# 08-STM32-01.net
KiCad netlist of a schematic drawn in Altium Designer
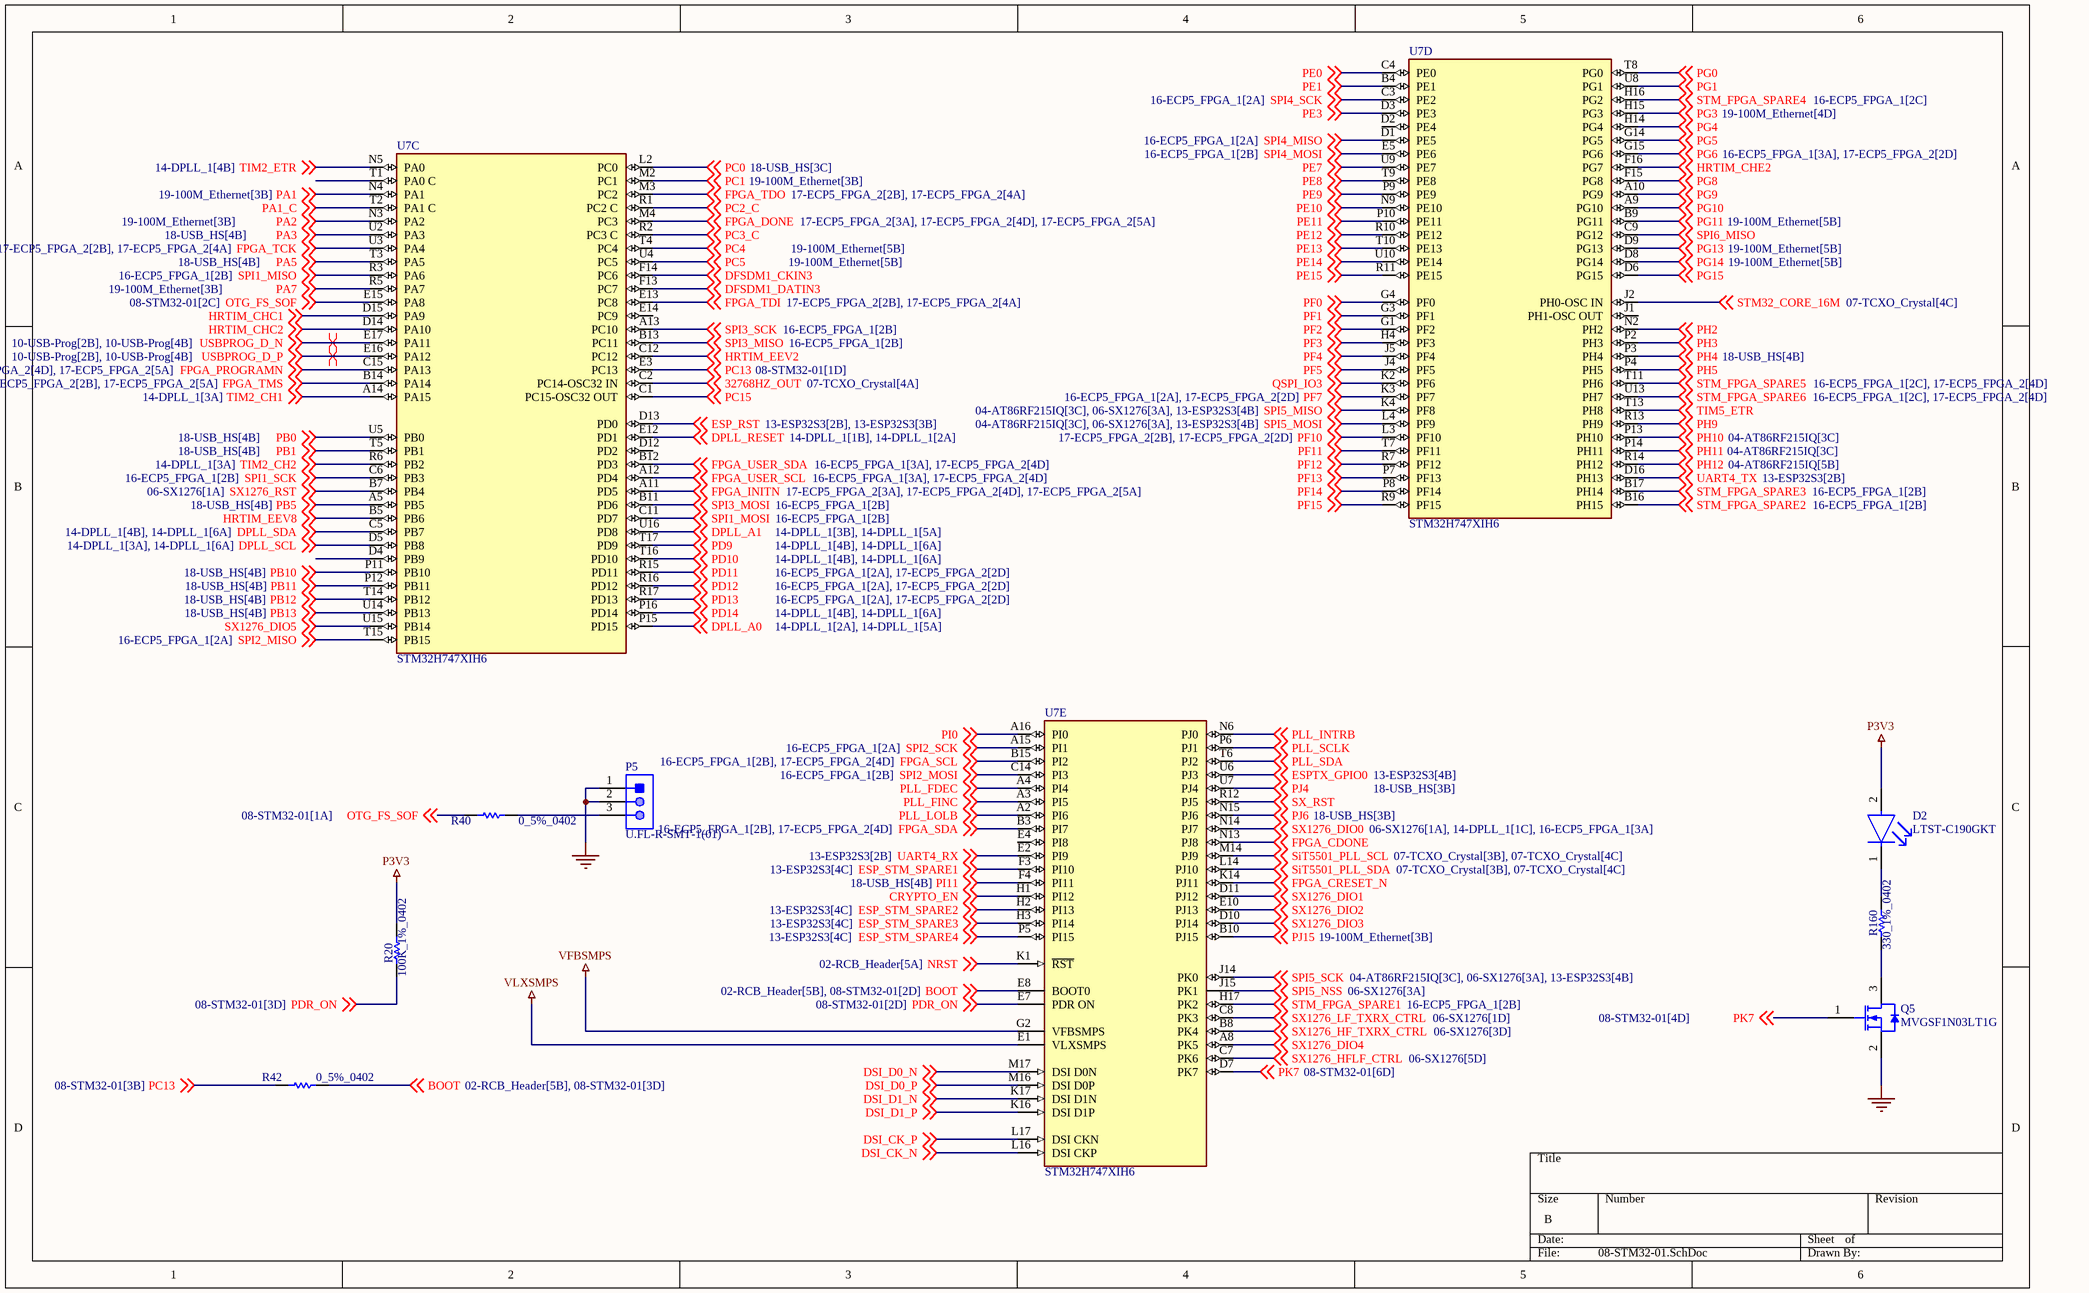
[diagram p0: 08-STM32-01.SchDoc]

(export (version "E")
  (design (tool "Eeschema 10.0.6"))
  (components
    (comp (ref "D2")
      (value "LTST-C190GKT")
      (footprint "FP-LTST-C190GKT-MFG")
      (description "LED GREEN CLEAR CHIP SMD")
      (fields (field (name "VOLTAGE") "2V"))
      (libsource (lib "Altium Content Vault") (part "8706943c75ba83719d021d2fdc84c58"))
    )
    (comp (ref "P5")
      (value "U.FL-R-SMT-1(01)")
      (footprint "HRS-U.FL-R-SMT-3_V")
      (description "Ultra Small Coaxial Connector, 6 GHz, -40 to 90 degC, 3-Pin SMD, RoHS, Bulk")
      (fields (field (name "MANUFACTURER") "Hirose Electric"))
      (libsource (lib "Altium Content Vault") (part "CN-1P-M-R3"))
    )
    (comp (ref "Q5")
      (value "MVGSF1N03LT1G")
      (footprint "ONSC-SOT-23-3-318-08_V")
      (description "Power MOSFET, 30 V, 2.1 A, Single N-Channel, 3-Pin SOT-23, Pb-Free, Tape and Reel")
      (fields (field (name "MANUFACTURER") "On Semiconductor"))
      (libsource (lib "Altium Content Vault") (part "ONSC-NMOS-G1S2D3-3"))
    )
    (comp (ref "R20")
      (value "100K_1%_0402")
      (footprint "RESC1005X40X25ML05T10")
      (fields (field (name "MANUFACTURER") "Yageo") (field (name "PART NUMBER") "RC0402FR-13100KL"))
      (libsource (lib "Altium Content Vault") (part "RES"))
    )
    (comp (ref "R40")
      (value "0_5%_0402")
      (footprint "RESC1005X40X25NL05T10")
      (fields (field (name "MANUFACTURER") "Panasonic") (field (name "PART NUMBER") "ERJ-U020R00X"))
      (libsource (lib "Altium Content Vault") (part "RES"))
    )
    (comp (ref "R42")
      (value "0_5%_0402")
      (footprint "RESC1005X40X25NL05T10")
      (fields (field (name "MANUFACTURER") "Panasonic") (field (name "PART NUMBER") "ERJ-U020R00X"))
      (libsource (lib "Altium Content Vault") (part "RES"))
    )
    (comp (ref "R160")
      (value "330_1%_0402")
      (footprint "RESC1005X40X25NL10T10")
      (fields (field (name "MANUFACTURER") "Panasonic") (field (name "PART NUMBER") "ERA-2AED331X"))
      (libsource (lib "Altium Content Vault") (part "RES"))
    )
    (comp (ref "U7")
      (value "STM32H747XIH6")
      (footprint "FP-TFBGA240+25-A07U-MFG")
      (description "HIGH-PERFORMANCE AND DSP WITH DP")
      (fields
        (field (name "MANUFACTURER") "STMicroelectronics")
        (field (name "OCTOPART") "https://octopart.com/stm32h747xih6-stmicroelectronics-100293943")
      )
      (libsource (lib "Altium Content Vault") (part "41f839bdfd00d9510c8672f0f410bfb"))
    )
  )
  (nets
    (net (code "1") (name "32768HZ_OUT") (class "Default")
      (node (ref "U7") (pin "C2") (pinfunction "PC14-OSC32_IN_C2") (pintype "bidirectional"))
    )
    (net (code "2") (name "BOOT") (class "Default")
      (node (ref "R42") (pin "2") (pinfunction "2_2") (pintype "passive"))
      (node (ref "U7") (pin "E8") (pinfunction "BOOT0_E8") (pintype "passive"))
    )
    (net (code "3") (name "CRYPTO_EN") (class "Default")
      (node (ref "U7") (pin "H1") (pinfunction "PI12_H1") (pintype "bidirectional"))
    )
    (net (code "4") (name "DFSDM1_CKIN3") (class "Default")
      (node (ref "U7") (pin "F14") (pinfunction "PC6_F14") (pintype "bidirectional"))
    )
    (net (code "5") (name "DFSDM1_DATIN3") (class "Default")
      (node (ref "U7") (pin "F13") (pinfunction "PC7_F13") (pintype "bidirectional"))
    )
    (net (code "6") (name "DPLL_A0") (class "Default")
      (node (ref "U7") (pin "P15") (pinfunction "PD15_P15") (pintype "bidirectional"))
    )
    (net (code "7") (name "DPLL_A1") (class "Default")
      (node (ref "U7") (pin "U16") (pinfunction "PD8_U16") (pintype "bidirectional"))
    )
    (net (code "8") (name "DPLL_RESET") (class "Default")
      (node (ref "U7") (pin "E12") (pinfunction "PD1_E12") (pintype "bidirectional"))
    )
    (net (code "9") (name "DPLL_SCL") (class "Default")
      (node (ref "U7") (pin "D5") (pinfunction "PB8_D5") (pintype "bidirectional"))
    )
    (net (code "10") (name "DPLL_SDA") (class "Default")
      (node (ref "U7") (pin "C5") (pinfunction "PB7_C5") (pintype "bidirectional"))
    )
    (net (code "11") (name "DSI_CK_N") (class "Default")
      (node (ref "U7") (pin "L16") (pinfunction "DSI_CKP_L16") (pintype "input"))
    )
    (net (code "12") (name "DSI_CK_P") (class "Default")
      (node (ref "U7") (pin "L17") (pinfunction "DSI_CKN_L17") (pintype "input"))
    )
    (net (code "13") (name "DSI_D0_N") (class "Default")
      (node (ref "U7") (pin "M17") (pinfunction "DSI_D0N_M17") (pintype "input"))
    )
    (net (code "14") (name "DSI_D0_P") (class "Default")
      (node (ref "U7") (pin "M16") (pinfunction "DSI_D0P_M16") (pintype "input"))
    )
    (net (code "15") (name "DSI_D1_N") (class "Default")
      (node (ref "U7") (pin "K17") (pinfunction "DSI_D1N_K17") (pintype "input"))
    )
    (net (code "16") (name "DSI_D1_P") (class "Default")
      (node (ref "U7") (pin "K16") (pinfunction "DSI_D1P_K16") (pintype "input"))
    )
    (net (code "17") (name "ESPTX_GPIO0") (class "Default")
      (node (ref "U7") (pin "U6") (pinfunction "PJ3_U6") (pintype "bidirectional"))
    )
    (net (code "18") (name "ESP_RST") (class "Default")
      (node (ref "U7") (pin "D13") (pinfunction "PD0_D13") (pintype "bidirectional"))
    )
    (net (code "19") (name "ESP_STM_SPARE1") (class "Default")
      (node (ref "U7") (pin "F3") (pinfunction "PI10_F3") (pintype "bidirectional"))
    )
    (net (code "20") (name "ESP_STM_SPARE2") (class "Default")
      (node (ref "U7") (pin "H2") (pinfunction "PI13_H2") (pintype "bidirectional"))
    )
    (net (code "21") (name "ESP_STM_SPARE3") (class "Default")
      (node (ref "U7") (pin "H3") (pinfunction "PI14_H3") (pintype "bidirectional"))
    )
    (net (code "22") (name "ESP_STM_SPARE4") (class "Default")
      (node (ref "U7") (pin "P5") (pinfunction "PI15_P5") (pintype "bidirectional"))
    )
    (net (code "23") (name "FPGA_CDONE") (class "Default")
      (node (ref "U7") (pin "N13") (pinfunction "PJ8_N13") (pintype "bidirectional"))
    )
    (net (code "24") (name "FPGA_CRESET_N") (class "Default")
      (node (ref "U7") (pin "K14") (pinfunction "PJ11_K14") (pintype "bidirectional"))
    )
    (net (code "25") (name "FPGA_DONE") (class "Default")
      (node (ref "U7") (pin "M4") (pinfunction "PC3_M4") (pintype "bidirectional"))
    )
    (net (code "26") (name "FPGA_INITN") (class "Default")
      (node (ref "U7") (pin "A11") (pinfunction "PD5_A11") (pintype "bidirectional"))
    )
    (net (code "27") (name "FPGA_PROGRAMN") (class "Default")
      (node (ref "U7") (pin "C15") (pinfunction "PA13_C15") (pintype "bidirectional"))
    )
    (net (code "28") (name "FPGA_SCL") (class "Default")
      (node (ref "U7") (pin "B15") (pinfunction "PI2_B15") (pintype "bidirectional"))
    )
    (net (code "29") (name "FPGA_SDA") (class "Default")
      (node (ref "U7") (pin "B3") (pinfunction "PI7_B3") (pintype "bidirectional"))
    )
    (net (code "30") (name "FPGA_TCK") (class "Default")
      (node (ref "U7") (pin "U3") (pinfunction "PA4_U3") (pintype "bidirectional"))
    )
    (net (code "31") (name "FPGA_TDI") (class "Default")
      (node (ref "U7") (pin "E13") (pinfunction "PC8_E13") (pintype "bidirectional"))
    )
    (net (code "32") (name "FPGA_TDO") (class "Default")
      (node (ref "U7") (pin "M3") (pinfunction "PC2_M3") (pintype "bidirectional"))
    )
    (net (code "33") (name "FPGA_TMS") (class "Default")
      (node (ref "U7") (pin "B14") (pinfunction "PA14_B14") (pintype "bidirectional"))
    )
    (net (code "34") (name "FPGA_USER_SCL") (class "Default")
      (node (ref "U7") (pin "A12") (pinfunction "PD4_A12") (pintype "bidirectional"))
    )
    (net (code "35") (name "FPGA_USER_SDA") (class "Default")
      (node (ref "U7") (pin "B12") (pinfunction "PD3_B12") (pintype "bidirectional"))
    )
    (net (code "36") (name "GND") (class "Default")
      (node (ref "P5") (pin "1") (pinfunction "1_1") (pintype "passive"))
      (node (ref "P5") (pin "2") (pinfunction "2_2") (pintype "passive"))
      (node (ref "Q5") (pin "2") (pinfunction "S_2") (pintype "passive"))
    )
    (net (code "37") (name "HRTIM_CHC1") (class "Default")
      (node (ref "U7") (pin "D15") (pinfunction "PA9_D15") (pintype "bidirectional"))
    )
    (net (code "38") (name "HRTIM_CHC2") (class "Default")
      (node (ref "U7") (pin "D14") (pinfunction "PA10_D14") (pintype "bidirectional"))
    )
    (net (code "39") (name "HRTIM_CHE2") (class "Default")
      (node (ref "U7") (pin "F16") (pinfunction "PG7_F16") (pintype "bidirectional"))
    )
    (net (code "40") (name "HRTIM_EEV2") (class "Default")
      (node (ref "U7") (pin "C12") (pinfunction "PC12_C12") (pintype "bidirectional"))
    )
    (net (code "41") (name "HRTIM_EEV8") (class "Default")
      (node (ref "U7") (pin "B5") (pinfunction "PB6_B5") (pintype "bidirectional"))
    )
    (net (code "42") (name "NRST") (class "Default")
      (node (ref "U7") (pin "K1") (pinfunction "~{RST}_K1") (pintype "input"))
    )
    (net (code "43") (name "Net-(D2-C)") (class "Default")
      (node (ref "D2") (pin "1") (pinfunction "C_1") (pintype "passive"))
      (node (ref "R160") (pin "2") (pinfunction "2_2") (pintype "passive"))
    )
    (net (code "44") (name "Net-(P5-Pad3)") (class "Default")
      (node (ref "P5") (pin "3") (pinfunction "3_3") (pintype "passive"))
      (node (ref "R40") (pin "2") (pinfunction "2_2") (pintype "passive"))
    )
    (net (code "45") (name "Net-(Q5-D)") (class "Default")
      (node (ref "Q5") (pin "3") (pinfunction "D_3") (pintype "passive"))
      (node (ref "R160") (pin "1") (pinfunction "1_1") (pintype "passive"))
    )
    (net (code "46") (name "OTG_FS_SOF") (class "Default")
      (node (ref "R40") (pin "1") (pinfunction "1_1") (pintype "passive"))
      (node (ref "U7") (pin "E15") (pinfunction "PA8_E15") (pintype "bidirectional"))
    )
    (net (code "47") (name "P3V3") (class "Default")
      (node (ref "D2") (pin "2") (pinfunction "A_2") (pintype "passive"))
      (node (ref "R20") (pin "2") (pinfunction "2_2") (pintype "passive"))
    )
    (net (code "48") (name "PA1") (class "Default")
      (node (ref "U7") (pin "N4") (pinfunction "PA1_N4") (pintype "bidirectional"))
    )
    (net (code "49") (name "PA1_C") (class "Default")
      (node (ref "U7") (pin "T2") (pinfunction "PA1_C_T2") (pintype "bidirectional"))
    )
    (net (code "50") (name "PA2") (class "Default")
      (node (ref "U7") (pin "N3") (pinfunction "PA2_N3") (pintype "bidirectional"))
    )
    (net (code "51") (name "PA3") (class "Default")
      (node (ref "U7") (pin "U2") (pinfunction "PA3_U2") (pintype "bidirectional"))
    )
    (net (code "52") (name "PA5") (class "Default")
      (node (ref "U7") (pin "T3") (pinfunction "PA5_T3") (pintype "bidirectional"))
    )
    (net (code "53") (name "PA7") (class "Default")
      (node (ref "U7") (pin "R5") (pinfunction "PA7_R5") (pintype "bidirectional"))
    )
    (net (code "54") (name "PB0") (class "Default")
      (node (ref "U7") (pin "U5") (pinfunction "PB0_U5") (pintype "bidirectional"))
    )
    (net (code "55") (name "PB1") (class "Default")
      (node (ref "U7") (pin "T5") (pinfunction "PB1_T5") (pintype "bidirectional"))
    )
    (net (code "56") (name "PB5") (class "Default")
      (node (ref "U7") (pin "A5") (pinfunction "PB5_A5") (pintype "bidirectional"))
    )
    (net (code "57") (name "PB10") (class "Default")
      (node (ref "U7") (pin "P11") (pinfunction "PB10_P11") (pintype "bidirectional"))
    )
    (net (code "58") (name "PB11") (class "Default")
      (node (ref "U7") (pin "P12") (pinfunction "PB11_P12") (pintype "bidirectional"))
    )
    (net (code "59") (name "PB12") (class "Default")
      (node (ref "U7") (pin "T14") (pinfunction "PB12_T14") (pintype "bidirectional"))
    )
    (net (code "60") (name "PB13") (class "Default")
      (node (ref "U7") (pin "U14") (pinfunction "PB13_U14") (pintype "bidirectional"))
    )
    (net (code "61") (name "PC0") (class "Default")
      (node (ref "U7") (pin "L2") (pinfunction "PC0_L2") (pintype "bidirectional"))
    )
    (net (code "62") (name "PC1") (class "Default")
      (node (ref "U7") (pin "M2") (pinfunction "PC1_M2") (pintype "bidirectional"))
    )
    (net (code "63") (name "PC2_C") (class "Default")
      (node (ref "U7") (pin "R1") (pinfunction "PC2_C_R1") (pintype "bidirectional"))
    )
    (net (code "64") (name "PC3_C") (class "Default")
      (node (ref "U7") (pin "R2") (pinfunction "PC3_C_R2") (pintype "bidirectional"))
    )
    (net (code "65") (name "PC4") (class "Default")
      (node (ref "U7") (pin "T4") (pinfunction "PC4_T4") (pintype "bidirectional"))
    )
    (net (code "66") (name "PC5") (class "Default")
      (node (ref "U7") (pin "U4") (pinfunction "PC5_U4") (pintype "bidirectional"))
    )
    (net (code "67") (name "PC13") (class "Default")
      (node (ref "R42") (pin "1") (pinfunction "1_1") (pintype "passive"))
      (node (ref "U7") (pin "E3") (pinfunction "PC13_E3") (pintype "bidirectional"))
    )
    (net (code "68") (name "PC15") (class "Default")
      (node (ref "U7") (pin "C1") (pinfunction "PC15-OSC32_OUT_C1") (pintype "bidirectional"))
    )
    (net (code "69") (name "PD9") (class "Default")
      (node (ref "U7") (pin "T17") (pinfunction "PD9_T17") (pintype "bidirectional"))
    )
    (net (code "70") (name "PD10") (class "Default")
      (node (ref "U7") (pin "T16") (pinfunction "PD10_T16") (pintype "bidirectional"))
    )
    (net (code "71") (name "PD11") (class "Default")
      (node (ref "U7") (pin "R15") (pinfunction "PD11_R15") (pintype "bidirectional"))
    )
    (net (code "72") (name "PD12") (class "Default")
      (node (ref "U7") (pin "R16") (pinfunction "PD12_R16") (pintype "bidirectional"))
    )
    (net (code "73") (name "PD13") (class "Default")
      (node (ref "U7") (pin "R17") (pinfunction "PD13_R17") (pintype "bidirectional"))
    )
    (net (code "74") (name "PD14") (class "Default")
      (node (ref "U7") (pin "P16") (pinfunction "PD14_P16") (pintype "bidirectional"))
    )
    (net (code "75") (name "PDR_ON") (class "Default")
      (node (ref "R20") (pin "1") (pinfunction "1_1") (pintype "passive"))
      (node (ref "U7") (pin "E7") (pinfunction "PDR_ON_E7") (pintype "power_in"))
    )
    (net (code "76") (name "PE0") (class "Default")
      (node (ref "U7") (pin "C4") (pinfunction "PE0_C4") (pintype "bidirectional"))
    )
    (net (code "77") (name "PE1") (class "Default")
      (node (ref "U7") (pin "B4") (pinfunction "PE1_B4") (pintype "bidirectional"))
    )
    (net (code "78") (name "PE3") (class "Default")
      (node (ref "U7") (pin "D3") (pinfunction "PE3_D3") (pintype "bidirectional"))
    )
    (net (code "79") (name "PE7") (class "Default")
      (node (ref "U7") (pin "U9") (pinfunction "PE7_U9") (pintype "bidirectional"))
    )
    (net (code "80") (name "PE8") (class "Default")
      (node (ref "U7") (pin "T9") (pinfunction "PE8_T9") (pintype "bidirectional"))
    )
    (net (code "81") (name "PE9") (class "Default")
      (node (ref "U7") (pin "P9") (pinfunction "PE9_P9") (pintype "bidirectional"))
    )
    (net (code "82") (name "PE10") (class "Default")
      (node (ref "U7") (pin "N9") (pinfunction "PE10_N9") (pintype "bidirectional"))
    )
    (net (code "83") (name "PE11") (class "Default")
      (node (ref "U7") (pin "P10") (pinfunction "PE11_P10") (pintype "bidirectional"))
    )
    (net (code "84") (name "PE12") (class "Default")
      (node (ref "U7") (pin "R10") (pinfunction "PE12_R10") (pintype "bidirectional"))
    )
    (net (code "85") (name "PE13") (class "Default")
      (node (ref "U7") (pin "T10") (pinfunction "PE13_T10") (pintype "bidirectional"))
    )
    (net (code "86") (name "PE14") (class "Default")
      (node (ref "U7") (pin "U10") (pinfunction "PE14_U10") (pintype "bidirectional"))
    )
    (net (code "87") (name "PE15") (class "Default")
      (node (ref "U7") (pin "R11") (pinfunction "PE15_R11") (pintype "bidirectional"))
    )
    (net (code "88") (name "PF0") (class "Default")
      (node (ref "U7") (pin "G4") (pinfunction "PF0_G4") (pintype "bidirectional"))
    )
    (net (code "89") (name "PF1") (class "Default")
      (node (ref "U7") (pin "G3") (pinfunction "PF1_G3") (pintype "bidirectional"))
    )
    (net (code "90") (name "PF2") (class "Default")
      (node (ref "U7") (pin "G1") (pinfunction "PF2_G1") (pintype "bidirectional"))
    )
    (net (code "91") (name "PF3") (class "Default")
      (node (ref "U7") (pin "H4") (pinfunction "PF3_H4") (pintype "bidirectional"))
    )
    (net (code "92") (name "PF4") (class "Default")
      (node (ref "U7") (pin "J5") (pinfunction "PF4_J5") (pintype "bidirectional"))
    )
    (net (code "93") (name "PF5") (class "Default")
      (node (ref "U7") (pin "J4") (pinfunction "PF5_J4") (pintype "bidirectional"))
    )
    (net (code "94") (name "PF7") (class "Default")
      (node (ref "U7") (pin "K3") (pinfunction "PF7_K3") (pintype "bidirectional"))
    )
    (net (code "95") (name "PF10") (class "Default")
      (node (ref "U7") (pin "L3") (pinfunction "PF10_L3") (pintype "bidirectional"))
    )
    (net (code "96") (name "PF11") (class "Default")
      (node (ref "U7") (pin "T7") (pinfunction "PF11_T7") (pintype "bidirectional"))
    )
    (net (code "97") (name "PF12") (class "Default")
      (node (ref "U7") (pin "R7") (pinfunction "PF12_R7") (pintype "bidirectional"))
    )
    (net (code "98") (name "PF13") (class "Default")
      (node (ref "U7") (pin "P7") (pinfunction "PF13_P7") (pintype "bidirectional"))
    )
    (net (code "99") (name "PF14") (class "Default")
      (node (ref "U7") (pin "P8") (pinfunction "PF14_P8") (pintype "bidirectional"))
    )
    (net (code "100") (name "PF15") (class "Default")
      (node (ref "U7") (pin "R9") (pinfunction "PF15_R9") (pintype "bidirectional"))
    )
    (net (code "101") (name "PG0") (class "Default")
      (node (ref "U7") (pin "T8") (pinfunction "PG0_T8") (pintype "bidirectional"))
    )
    (net (code "102") (name "PG1") (class "Default")
      (node (ref "U7") (pin "U8") (pinfunction "PG1_U8") (pintype "bidirectional"))
    )
    (net (code "103") (name "PG3") (class "Default")
      (node (ref "U7") (pin "H15") (pinfunction "PG3_H15") (pintype "bidirectional"))
    )
    (net (code "104") (name "PG4") (class "Default")
      (node (ref "U7") (pin "H14") (pinfunction "PG4_H14") (pintype "bidirectional"))
    )
    (net (code "105") (name "PG5") (class "Default")
      (node (ref "U7") (pin "G14") (pinfunction "PG5_G14") (pintype "bidirectional"))
    )
    (net (code "106") (name "PG6") (class "Default")
      (node (ref "U7") (pin "G15") (pinfunction "PG6_G15") (pintype "bidirectional"))
    )
    (net (code "107") (name "PG8") (class "Default")
      (node (ref "U7") (pin "F15") (pinfunction "PG8_F15") (pintype "bidirectional"))
    )
    (net (code "108") (name "PG9") (class "Default")
      (node (ref "U7") (pin "A10") (pinfunction "PG9_A10") (pintype "bidirectional"))
    )
    (net (code "109") (name "PG10") (class "Default")
      (node (ref "U7") (pin "A9") (pinfunction "PG10_A9") (pintype "bidirectional"))
    )
    (net (code "110") (name "PG11") (class "Default")
      (node (ref "U7") (pin "B9") (pinfunction "PG11_B9") (pintype "bidirectional"))
    )
    (net (code "111") (name "PG13") (class "Default")
      (node (ref "U7") (pin "D9") (pinfunction "PG13_D9") (pintype "bidirectional"))
    )
    (net (code "112") (name "PG14") (class "Default")
      (node (ref "U7") (pin "D8") (pinfunction "PG14_D8") (pintype "bidirectional"))
    )
    (net (code "113") (name "PG15") (class "Default")
      (node (ref "U7") (pin "D6") (pinfunction "PG15_D6") (pintype "bidirectional"))
    )
    (net (code "114") (name "PH2") (class "Default")
      (node (ref "U7") (pin "N2") (pinfunction "PH2_N2") (pintype "bidirectional"))
    )
    (net (code "115") (name "PH3") (class "Default")
      (node (ref "U7") (pin "P2") (pinfunction "PH3_P2") (pintype "bidirectional"))
    )
    (net (code "116") (name "PH4") (class "Default")
      (node (ref "U7") (pin "P3") (pinfunction "PH4_P3") (pintype "bidirectional"))
    )
    (net (code "117") (name "PH5") (class "Default")
      (node (ref "U7") (pin "P4") (pinfunction "PH5_P4") (pintype "bidirectional"))
    )
    (net (code "118") (name "PH9") (class "Default")
      (node (ref "U7") (pin "R13") (pinfunction "PH9_R13") (pintype "bidirectional"))
    )
    (net (code "119") (name "PH10") (class "Default")
      (node (ref "U7") (pin "P13") (pinfunction "PH10_P13") (pintype "bidirectional"))
    )
    (net (code "120") (name "PH11") (class "Default")
      (node (ref "U7") (pin "P14") (pinfunction "PH11_P14") (pintype "bidirectional"))
    )
    (net (code "121") (name "PH12") (class "Default")
      (node (ref "U7") (pin "R14") (pinfunction "PH12_R14") (pintype "bidirectional"))
    )
    (net (code "122") (name "PI0") (class "Default")
      (node (ref "U7") (pin "A16") (pinfunction "PI0_A16") (pintype "bidirectional"))
    )
    (net (code "123") (name "PI11") (class "Default")
      (node (ref "U7") (pin "F4") (pinfunction "PI11_F4") (pintype "bidirectional"))
    )
    (net (code "124") (name "PJ4") (class "Default")
      (node (ref "U7") (pin "U7") (pinfunction "PJ4_U7") (pintype "bidirectional"))
    )
    (net (code "125") (name "PJ6") (class "Default")
      (node (ref "U7") (pin "N15") (pinfunction "PJ6_N15") (pintype "bidirectional"))
    )
    (net (code "126") (name "PJ15") (class "Default")
      (node (ref "U7") (pin "B10") (pinfunction "PJ15_B10") (pintype "bidirectional"))
    )
    (net (code "127") (name "PK7") (class "Default")
      (node (ref "Q5") (pin "1") (pinfunction "G_1") (pintype "passive"))
      (node (ref "U7") (pin "D7") (pinfunction "PK7_D7") (pintype "bidirectional"))
    )
    (net (code "128") (name "PLL_FDEC") (class "Default")
      (node (ref "U7") (pin "A4") (pinfunction "PI4_A4") (pintype "bidirectional"))
    )
    (net (code "129") (name "PLL_FINC") (class "Default")
      (node (ref "U7") (pin "A3") (pinfunction "PI5_A3") (pintype "bidirectional"))
    )
    (net (code "130") (name "PLL_INTRB") (class "Default")
      (node (ref "U7") (pin "N6") (pinfunction "PJ0_N6") (pintype "bidirectional"))
    )
    (net (code "131") (name "PLL_LOLB") (class "Default")
      (node (ref "U7") (pin "A2") (pinfunction "PI6_A2") (pintype "bidirectional"))
    )
    (net (code "132") (name "PLL_SCLK") (class "Default")
      (node (ref "U7") (pin "P6") (pinfunction "PJ1_P6") (pintype "bidirectional"))
    )
    (net (code "133") (name "PLL_SDA") (class "Default")
      (node (ref "U7") (pin "T6") (pinfunction "PJ2_T6") (pintype "bidirectional"))
    )
    (net (code "134") (name "QSPI_IO3") (class "Default")
      (node (ref "U7") (pin "K2") (pinfunction "PF6_K2") (pintype "bidirectional"))
    )
    (net (code "135") (name "SPI1_MISO") (class "Default")
      (node (ref "U7") (pin "R3") (pinfunction "PA6_R3") (pintype "bidirectional"))
    )
    (net (code "136") (name "SPI1_MOSI") (class "Default")
      (node (ref "U7") (pin "C11") (pinfunction "PD7_C11") (pintype "bidirectional"))
    )
    (net (code "137") (name "SPI1_SCK") (class "Default")
      (node (ref "U7") (pin "C6") (pinfunction "PB3_C6") (pintype "bidirectional"))
    )
    (net (code "138") (name "SPI2_MISO") (class "Default")
      (node (ref "U7") (pin "T15") (pinfunction "PB15_T15") (pintype "bidirectional"))
    )
    (net (code "139") (name "SPI2_MOSI") (class "Default")
      (node (ref "U7") (pin "C14") (pinfunction "PI3_C14") (pintype "bidirectional"))
    )
    (net (code "140") (name "SPI2_SCK") (class "Default")
      (node (ref "U7") (pin "A15") (pinfunction "PI1_A15") (pintype "bidirectional"))
    )
    (net (code "141") (name "SPI3_MISO") (class "Default")
      (node (ref "U7") (pin "B13") (pinfunction "PC11_B13") (pintype "bidirectional"))
    )
    (net (code "142") (name "SPI3_MOSI") (class "Default")
      (node (ref "U7") (pin "B11") (pinfunction "PD6_B11") (pintype "bidirectional"))
    )
    (net (code "143") (name "SPI3_SCK") (class "Default")
      (node (ref "U7") (pin "A13") (pinfunction "PC10_A13") (pintype "bidirectional"))
    )
    (net (code "144") (name "SPI4_MISO") (class "Default")
      (node (ref "U7") (pin "D1") (pinfunction "PE5_D1") (pintype "bidirectional"))
    )
    (net (code "145") (name "SPI4_MOSI") (class "Default")
      (node (ref "U7") (pin "E5") (pinfunction "PE6_E5") (pintype "bidirectional"))
    )
    (net (code "146") (name "SPI4_SCK") (class "Default")
      (node (ref "U7") (pin "C3") (pinfunction "PE2_C3") (pintype "bidirectional"))
    )
    (net (code "147") (name "SPI5_MISO") (class "Default")
      (node (ref "U7") (pin "K4") (pinfunction "PF8_K4") (pintype "bidirectional"))
    )
    (net (code "148") (name "SPI5_MOSI") (class "Default")
      (node (ref "U7") (pin "L4") (pinfunction "PF9_L4") (pintype "bidirectional"))
    )
    (net (code "149") (name "SPI5_NSS") (class "Default")
      (node (ref "U7") (pin "J15") (pinfunction "PK1_J15") (pintype "passive"))
    )
    (net (code "150") (name "SPI5_SCK") (class "Default")
      (node (ref "U7") (pin "J14") (pinfunction "PK0_J14") (pintype "bidirectional"))
    )
    (net (code "151") (name "SPI6_MISO") (class "Default")
      (node (ref "U7") (pin "C9") (pinfunction "PG12_C9") (pintype "bidirectional"))
    )
    (net (code "152") (name "STM32_CORE_16M") (class "Default")
      (node (ref "U7") (pin "J2") (pinfunction "PH0-OSC_IN_J2") (pintype "bidirectional"))
    )
    (net (code "153") (name "STM_FPGA_SPARE1") (class "Default")
      (node (ref "U7") (pin "H17") (pinfunction "PK2_H17") (pintype "bidirectional"))
    )
    (net (code "154") (name "STM_FPGA_SPARE2") (class "Default")
      (node (ref "U7") (pin "B16") (pinfunction "PH15_B16") (pintype "bidirectional"))
    )
    (net (code "155") (name "STM_FPGA_SPARE3") (class "Default")
      (node (ref "U7") (pin "B17") (pinfunction "PH14_B17") (pintype "bidirectional"))
    )
    (net (code "156") (name "STM_FPGA_SPARE4") (class "Default")
      (node (ref "U7") (pin "H16") (pinfunction "PG2_H16") (pintype "bidirectional"))
    )
    (net (code "157") (name "STM_FPGA_SPARE5") (class "Default")
      (node (ref "U7") (pin "T11") (pinfunction "PH6_T11") (pintype "bidirectional"))
    )
    (net (code "158") (name "STM_FPGA_SPARE6") (class "Default")
      (node (ref "U7") (pin "U13") (pinfunction "PH7_U13") (pintype "bidirectional"))
    )
    (net (code "159") (name "SX1276_DIO0") (class "Default")
      (node (ref "U7") (pin "N14") (pinfunction "PJ7_N14") (pintype "bidirectional"))
    )
    (net (code "160") (name "SX1276_DIO1") (class "Default")
      (node (ref "U7") (pin "D11") (pinfunction "PJ12_D11") (pintype "bidirectional"))
    )
    (net (code "161") (name "SX1276_DIO2") (class "Default")
      (node (ref "U7") (pin "E10") (pinfunction "PJ13_E10") (pintype "bidirectional"))
    )
    (net (code "162") (name "SX1276_DIO3") (class "Default")
      (node (ref "U7") (pin "D10") (pinfunction "PJ14_D10") (pintype "bidirectional"))
    )
    (net (code "163") (name "SX1276_DIO4") (class "Default")
      (node (ref "U7") (pin "A8") (pinfunction "PK5_A8") (pintype "bidirectional"))
    )
    (net (code "164") (name "SX1276_DIO5") (class "Default")
      (node (ref "U7") (pin "U15") (pinfunction "PB14_U15") (pintype "bidirectional"))
    )
    (net (code "165") (name "SX1276_HFLF_CTRL") (class "Default")
      (node (ref "U7") (pin "C7") (pinfunction "PK6_C7") (pintype "bidirectional"))
    )
    (net (code "166") (name "SX1276_HF_TXRX_CTRL") (class "Default")
      (node (ref "U7") (pin "B8") (pinfunction "PK4_B8") (pintype "bidirectional"))
    )
    (net (code "167") (name "SX1276_LF_TXRX_CTRL") (class "Default")
      (node (ref "U7") (pin "C8") (pinfunction "PK3_C8") (pintype "bidirectional"))
    )
    (net (code "168") (name "SX1276_RST") (class "Default")
      (node (ref "U7") (pin "B7") (pinfunction "PB4_B7") (pintype "bidirectional"))
    )
    (net (code "169") (name "SX_RST") (class "Default")
      (node (ref "U7") (pin "R12") (pinfunction "PJ5_R12") (pintype "bidirectional"))
    )
    (net (code "170") (name "SiT5501_PLL_SCL") (class "Default")
      (node (ref "U7") (pin "M14") (pinfunction "PJ9_M14") (pintype "bidirectional"))
    )
    (net (code "171") (name "SiT5501_PLL_SDA") (class "Default")
      (node (ref "U7") (pin "L14") (pinfunction "PJ10_L14") (pintype "bidirectional"))
    )
    (net (code "172") (name "TIM2_CH1") (class "Default")
      (node (ref "U7") (pin "A14") (pinfunction "PA15_A14") (pintype "bidirectional"))
    )
    (net (code "173") (name "TIM2_CH2") (class "Default")
      (node (ref "U7") (pin "R6") (pinfunction "PB2_R6") (pintype "bidirectional"))
    )
    (net (code "174") (name "TIM2_ETR") (class "Default")
      (node (ref "U7") (pin "N5") (pinfunction "PA0_N5") (pintype "bidirectional"))
    )
    (net (code "175") (name "TIM5_ETR") (class "Default")
      (node (ref "U7") (pin "T13") (pinfunction "PH8_T13") (pintype "bidirectional"))
    )
    (net (code "176") (name "UART4_RX") (class "Default")
      (node (ref "U7") (pin "E2") (pinfunction "PI9_E2") (pintype "bidirectional"))
    )
    (net (code "177") (name "UART4_TX") (class "Default")
      (node (ref "U7") (pin "D16") (pinfunction "PH13_D16") (pintype "bidirectional"))
    )
    (net (code "178") (name "USBPROG_D_N") (class "Default")
      (node (ref "U7") (pin "E17") (pinfunction "PA11_E17") (pintype "bidirectional"))
    )
    (net (code "179") (name "USBPROG_D_P") (class "Default")
      (node (ref "U7") (pin "E16") (pinfunction "PA12_E16") (pintype "bidirectional"))
    )
    (net (code "180") (name "VFBSMPS") (class "Default")
      (node (ref "U7") (pin "G2") (pinfunction "VFBSMPS_G2") (pintype "power_in"))
    )
    (net (code "181") (name "VLXSMPS") (class "Default")
      (node (ref "U7") (pin "E1") (pinfunction "VLXSMPS_E1") (pintype "power_in"))
    )
    (net (code "182") (name "unconnected-(U7C-PA0_C-PadT1)") (class "Default")
      (node (ref "U7") (pin "T1") (pinfunction "PA0_C_T1") (pintype "bidirectional"))
    )
    (net (code "183") (name "unconnected-(U7C-PB9-PadD4)") (class "Default")
      (node (ref "U7") (pin "D4") (pinfunction "PB9_D4") (pintype "bidirectional"))
    )
    (net (code "184") (name "unconnected-(U7C-PC9-PadE14)") (class "Default")
      (node (ref "U7") (pin "E14") (pinfunction "PC9_E14") (pintype "bidirectional"))
    )
    (net (code "185") (name "unconnected-(U7C-PD2-PadD12)") (class "Default")
      (node (ref "U7") (pin "D12") (pinfunction "PD2_D12") (pintype "bidirectional"))
    )
    (net (code "186") (name "unconnected-(U7D-PE4-PadD2)") (class "Default")
      (node (ref "U7") (pin "D2") (pinfunction "PE4_D2") (pintype "bidirectional"))
    )
    (net (code "187") (name "unconnected-(U7D-PH1-OSC_OUT-PadJ1)") (class "Default")
      (node (ref "U7") (pin "J1") (pinfunction "PH1-OSC_OUT_J1") (pintype "bidirectional"))
    )
    (net (code "188") (name "unconnected-(U7E-PI8-PadE4)") (class "Default")
      (node (ref "U7") (pin "E4") (pinfunction "PI8_E4") (pintype "bidirectional"))
    )
  )
)
